# 1-Schematic_SumoBot.net
KiCad netlist of a schematic drawn in EasyEDA
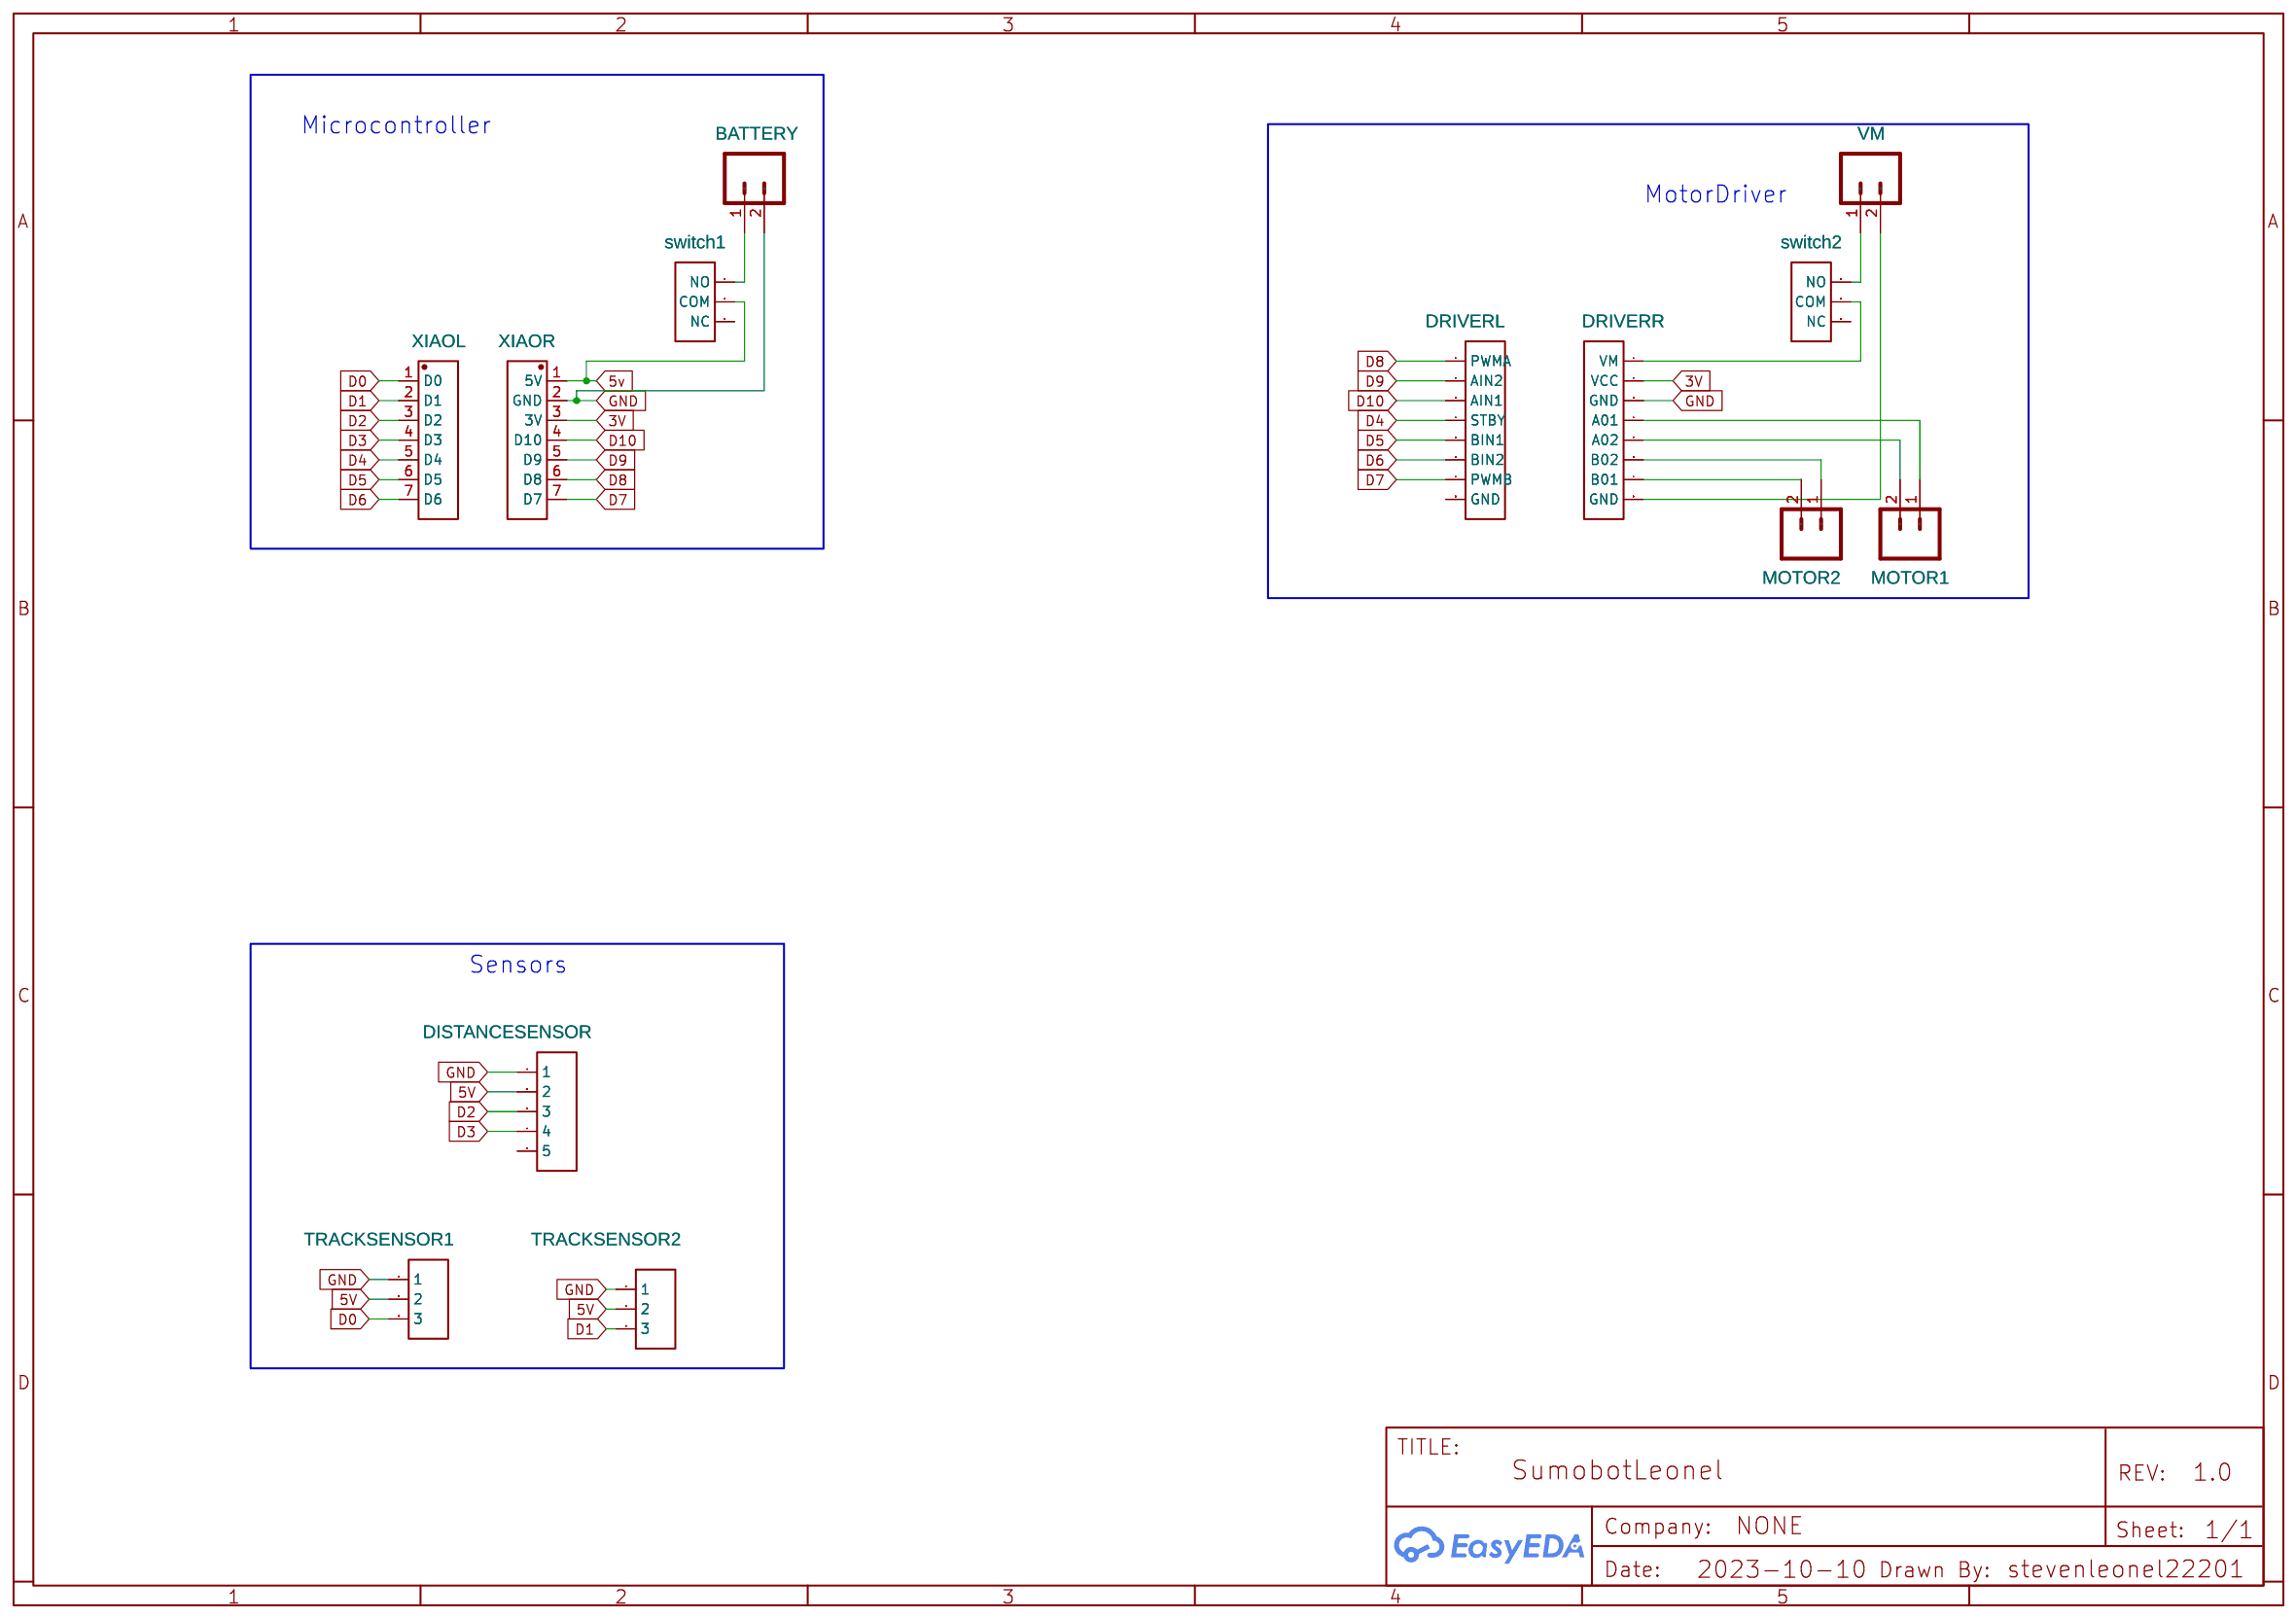
[diagram p0: schematic sheet]

(export (version "E")
  (design (tool "Eeschema 10.0.6"))
  (components
    (comp (ref "BATTERY") (value "NO") (libsource (lib "") (part "M025MM_1")))
    (comp (ref "DISTANCESENSOR")
      (value "Header-Female-2.54_1x5")
      (fields (field (name "Manufacturer Part") "2.54-1*5P母") (field (name "Manufacturer") "BOOMELE(博穆精密)"))
      (libsource (lib "") (part "Header-Female-2.54_1x5"))
    )
    (comp (ref "DRIVERL")
      (value "TB6612FNG left")
      (fields (field (name "Manufacturer Part") "2.54-1*8P母环保") (field (name "Manufacturer") "BOOMELE(博穆精密)"))
      (libsource (lib "") (part "Header-Female-2.54_1x8"))
    )
    (comp (ref "DRIVERR")
      (value "TB6612FNG rigth")
      (fields (field (name "Manufacturer Part") "2.54-1*8P母环保") (field (name "Manufacturer") "BOOMELE(博穆精密)"))
      (libsource (lib "") (part "Header-Female-2.54_1x8_1"))
    )
    (comp (ref "MOTOR1") (value "NO") (libsource (lib "") (part "M025MM_2")))
    (comp (ref "MOTOR2") (value "NO") (libsource (lib "") (part "M025MM_2")))
    (comp (ref "P1")
      (value "TRACKSENSOR1")
      (fields (field (name "Manufacturer Part") "2.54-1*3P母") (field (name "Manufacturer") "BOOMELE(博穆精密)"))
      (libsource (lib "") (part "Header-Female-2.54_1x3"))
    )
    (comp (ref "P2")
      (value "TRACKSENSOR2")
      (fields (field (name "Manufacturer Part") "2.54-1*3P母") (field (name "Manufacturer") "BOOMELE(博穆精密)"))
      (libsource (lib "") (part "Header-Female-2.54_1x3"))
    )
    (comp (ref "P3")
      (value "switch1")
      (fields (field (name "Manufacturer Part") "2.54-1*3P母") (field (name "Manufacturer") "BOOMELE(博穆精密)"))
      (libsource (lib "") (part "Header-Female-2.54_1x3_1"))
    )
    (comp (ref "P4")
      (value "switch2")
      (fields (field (name "Manufacturer Part") "2.54-1*3P母") (field (name "Manufacturer") "BOOMELE(博穆精密)"))
      (libsource (lib "") (part "Header-Female-2.54_1x3_1"))
    )
    (comp (ref "VM") (value "NO") (libsource (lib "") (part "M025MM")))
    (comp (ref "XIAOL") (value "PIN HEADER - 1X7") (libsource (lib "") (part "PIN HEADER - 1X7_1")))
    (comp (ref "XIAOR") (value "PIN HEADER - 1X7") (libsource (lib "") (part "PIN HEADER - 1X7")))
  )
  (nets
    (net (code "1") (name "3V") (class "Default")
      (node (ref "DRIVERR") (pin "2") (pinfunction "VCC_2") (pintype "input"))
      (node (ref "XIAOR") (pin "3") (pinfunction "3V_3") (pintype "unspecified"))
    )
    (net (code "2") (name "5V") (class "Default")
      (node (ref "DISTANCESENSOR") (pin "2") (pinfunction "2_2") (pintype "input"))
      (node (ref "P1") (pin "2") (pinfunction "2_2") (pintype "input"))
      (node (ref "P2") (pin "2") (pinfunction "2_2") (pintype "input"))
    )
    (net (code "3") (name "5v") (class "Default")
      (node (ref "P3") (pin "2") (pinfunction "COM_2") (pintype "input"))
      (node (ref "XIAOR") (pin "1") (pinfunction "5V_1") (pintype "unspecified"))
    )
    (net (code "4") (name "D0") (class "Default")
      (node (ref "P1") (pin "3") (pinfunction "3_3") (pintype "input"))
      (node (ref "XIAOL") (pin "1") (pinfunction "D0_1") (pintype "unspecified"))
    )
    (net (code "5") (name "D1") (class "Default")
      (node (ref "P2") (pin "3") (pinfunction "3_3") (pintype "input"))
      (node (ref "XIAOL") (pin "2") (pinfunction "D1_2") (pintype "unspecified"))
    )
    (net (code "6") (name "D2") (class "Default")
      (node (ref "DISTANCESENSOR") (pin "3") (pinfunction "3_3") (pintype "input"))
      (node (ref "XIAOL") (pin "3") (pinfunction "D2_3") (pintype "unspecified"))
    )
    (net (code "7") (name "D3") (class "Default")
      (node (ref "DISTANCESENSOR") (pin "4") (pinfunction "4_4") (pintype "input"))
      (node (ref "XIAOL") (pin "4") (pinfunction "D3_4") (pintype "unspecified"))
    )
    (net (code "8") (name "D4") (class "Default")
      (node (ref "DRIVERL") (pin "4") (pinfunction "STBY_4") (pintype "input"))
      (node (ref "XIAOL") (pin "5") (pinfunction "D4_5") (pintype "unspecified"))
    )
    (net (code "9") (name "D5") (class "Default")
      (node (ref "DRIVERL") (pin "5") (pinfunction "BIN1_5") (pintype "input"))
      (node (ref "XIAOL") (pin "6") (pinfunction "D5_6") (pintype "unspecified"))
    )
    (net (code "10") (name "D6") (class "Default")
      (node (ref "DRIVERL") (pin "6") (pinfunction "BIN2_6") (pintype "input"))
      (node (ref "XIAOL") (pin "7") (pinfunction "D6_7") (pintype "unspecified"))
    )
    (net (code "11") (name "D7") (class "Default")
      (node (ref "DRIVERL") (pin "7") (pinfunction "PWMB_7") (pintype "input"))
      (node (ref "XIAOR") (pin "7") (pinfunction "D7_7") (pintype "unspecified"))
    )
    (net (code "12") (name "D8") (class "Default")
      (node (ref "DRIVERL") (pin "1") (pinfunction "PWMA_1") (pintype "input"))
      (node (ref "XIAOR") (pin "6") (pinfunction "D8_6") (pintype "unspecified"))
    )
    (net (code "13") (name "D9") (class "Default")
      (node (ref "DRIVERL") (pin "2") (pinfunction "AIN2_2") (pintype "input"))
      (node (ref "XIAOR") (pin "5") (pinfunction "D9_5") (pintype "unspecified"))
    )
    (net (code "14") (name "D10") (class "Default")
      (node (ref "DRIVERL") (pin "3") (pinfunction "AIN1_3") (pintype "input"))
      (node (ref "XIAOR") (pin "4") (pinfunction "D10_4") (pintype "unspecified"))
    )
    (net (code "15") (name "GND") (class "Default")
      (node (ref "BATTERY") (pin "2") (pinfunction "2_2") (pintype "unspecified"))
      (node (ref "DISTANCESENSOR") (pin "1") (pinfunction "1_1") (pintype "input"))
      (node (ref "DRIVERR") (pin "3") (pinfunction "GND_3") (pintype "input"))
      (node (ref "P1") (pin "1") (pinfunction "1_1") (pintype "input"))
      (node (ref "P2") (pin "1") (pinfunction "1_1") (pintype "input"))
      (node (ref "XIAOR") (pin "2") (pinfunction "GND_2") (pintype "unspecified"))
    )
    (net (code "16") (name "Net-(DRIVERR-A01)") (class "Default")
      (node (ref "DRIVERR") (pin "4") (pinfunction "A01_4") (pintype "input"))
      (node (ref "MOTOR1") (pin "1") (pinfunction "1_1") (pintype "unspecified"))
    )
    (net (code "17") (name "Net-(DRIVERR-A02)") (class "Default")
      (node (ref "DRIVERR") (pin "5") (pinfunction "A02_5") (pintype "input"))
      (node (ref "MOTOR1") (pin "2") (pinfunction "2_2") (pintype "unspecified"))
    )
    (net (code "18") (name "Net-(DRIVERR-B01)") (class "Default")
      (node (ref "DRIVERR") (pin "7") (pinfunction "B01_7") (pintype "input"))
      (node (ref "MOTOR2") (pin "2") (pinfunction "2_2") (pintype "unspecified"))
    )
    (net (code "19") (name "Net-(DRIVERR-B02)") (class "Default")
      (node (ref "DRIVERR") (pin "6") (pinfunction "B02_6") (pintype "input"))
      (node (ref "MOTOR2") (pin "1") (pinfunction "1_1") (pintype "unspecified"))
    )
    (net (code "20") (name "Net-(DRIVERR-GND-Pad8)") (class "Default")
      (node (ref "DRIVERR") (pin "8") (pinfunction "GND_8") (pintype "input"))
      (node (ref "VM") (pin "2") (pinfunction "2_2") (pintype "unspecified"))
    )
    (net (code "21") (name "Net-(DRIVERR-VM)") (class "Default")
      (node (ref "DRIVERR") (pin "1") (pinfunction "VM_1") (pintype "input"))
      (node (ref "P4") (pin "2") (pinfunction "COM_2") (pintype "input"))
    )
    (net (code "22") (name "Net-(P3-NO)") (class "Default")
      (node (ref "BATTERY") (pin "1") (pinfunction "1_1") (pintype "unspecified"))
      (node (ref "P3") (pin "1") (pinfunction "NO_1") (pintype "input"))
    )
    (net (code "23") (name "Net-(P4-NO)") (class "Default")
      (node (ref "P4") (pin "1") (pinfunction "NO_1") (pintype "input"))
      (node (ref "VM") (pin "1") (pinfunction "1_1") (pintype "unspecified"))
    )
    (net (code "24") (name "unconnected-(DISTANCESENSOR-Pad5)") (class "Default")
      (node (ref "DISTANCESENSOR") (pin "5") (pinfunction "5_5") (pintype "input"))
    )
    (net (code "25") (name "unconnected-(DRIVERL-GND-Pad8)") (class "Default")
      (node (ref "DRIVERL") (pin "8") (pinfunction "GND_8") (pintype "input"))
    )
    (net (code "26") (name "unconnected-(P3-NC-Pad3)") (class "Default")
      (node (ref "P3") (pin "3") (pinfunction "NC_3") (pintype "input"))
    )
    (net (code "27") (name "unconnected-(P4-NC-Pad3)") (class "Default")
      (node (ref "P4") (pin "3") (pinfunction "NC_3") (pintype "input"))
    )
  )
)
